# dogtag.net
KiCad netlist of a schematic drawn in Altium Designer
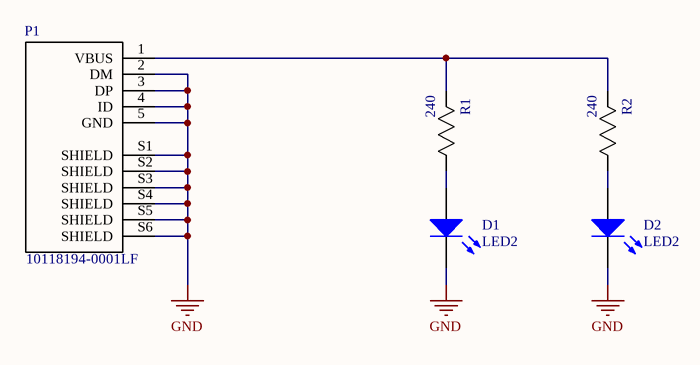
[diagram p0: dogtag.SchDoc]

(export (version "E")
  (design (tool "Eeschema 10.0.6"))
  (components
    (comp (ref "D1")
      (value "LED2")
      (footprint "3.2X1.6X1.1")
      (description "Typical RED, GREEN, YELLOW, AMBER GaAs LED")
      (libsource (lib "AltiumLibraries") (part "LED RED SMD"))
    )
    (comp (ref "D2")
      (value "LED2")
      (footprint "3.2X1.6X1.1")
      (description "Typical RED, GREEN, YELLOW, AMBER GaAs LED")
      (libsource (lib "AltiumLibraries") (part "LED RED SMD"))
    )
    (comp (ref "P1")
      (value "10118194-0001LF")
      (footprint "USB Micro B Receptacle")
      (description "USB - micro B USB 2.0 Receptacle Connector 5 Position Surface Mount, Right Angle; Through Hole")
      (fields (field (name "MF") "Amphenol ICC (FCI)"))
      (libsource (lib "AltiumLibraries") (part "USB Micro B Receptacle"))
    )
    (comp (ref "R1")
      (value "240")
      (footprint "0805")
      (description "RES SMD 240 OHM 5% 1/8W 0805")
      (fields (field (name "TOLERANCE") "5%"))
      (libsource (lib "AltiumLibraries") (part "RES 240.0 1/8W"))
    )
    (comp (ref "R2")
      (value "240")
      (footprint "0805")
      (description "RES SMD 240 OHM 5% 1/8W 0805")
      (fields (field (name "TOLERANCE") "5%"))
      (libsource (lib "AltiumLibraries") (part "RES 240.0 1/8W"))
    )
  )
  (nets
    (net (code "1") (name "GND") (class "Default")
      (node (ref "D1") (pin "2") (pinfunction "K_2") (pintype "passive"))
      (node (ref "D2") (pin "2") (pinfunction "K_2") (pintype "passive"))
      (node (ref "P1") (pin "2") (pinfunction "DM_2") (pintype "passive"))
      (node (ref "P1") (pin "3") (pinfunction "DP_3") (pintype "passive"))
      (node (ref "P1") (pin "4") (pinfunction "ID_4") (pintype "passive"))
      (node (ref "P1") (pin "5") (pinfunction "GND_5") (pintype "passive"))
      (node (ref "P1") (pin "S1") (pinfunction "SHIELD_S1") (pintype "passive"))
      (node (ref "P1") (pin "S2") (pinfunction "SHIELD_S2") (pintype "passive"))
      (node (ref "P1") (pin "S3") (pinfunction "SHIELD_S3") (pintype "passive"))
      (node (ref "P1") (pin "S4") (pinfunction "SHIELD_S4") (pintype "passive"))
      (node (ref "P1") (pin "S5") (pinfunction "SHIELD_S5") (pintype "passive"))
      (node (ref "P1") (pin "S6") (pinfunction "SHIELD_S6") (pintype "passive"))
    )
    (net (code "2") (name "Net-(D1-A)") (class "Default")
      (node (ref "D1") (pin "1") (pinfunction "A_1") (pintype "passive"))
      (node (ref "R1") (pin "1") (pinfunction "R1_1") (pintype "passive"))
    )
    (net (code "3") (name "Net-(D2-A)") (class "Default")
      (node (ref "D2") (pin "1") (pinfunction "A_1") (pintype "passive"))
      (node (ref "R2") (pin "1") (pinfunction "R1_1") (pintype "passive"))
    )
    (net (code "4") (name "Net-(P1-VBUS)") (class "Default")
      (node (ref "P1") (pin "1") (pinfunction "VBUS_1") (pintype "passive"))
      (node (ref "R1") (pin "2") (pinfunction "R2_2") (pintype "passive"))
      (node (ref "R2") (pin "2") (pinfunction "R2_2") (pintype "passive"))
    )
  )
)
